# DigitDisplayBoard.net
KiCad netlist of a schematic drawn in EAGLE
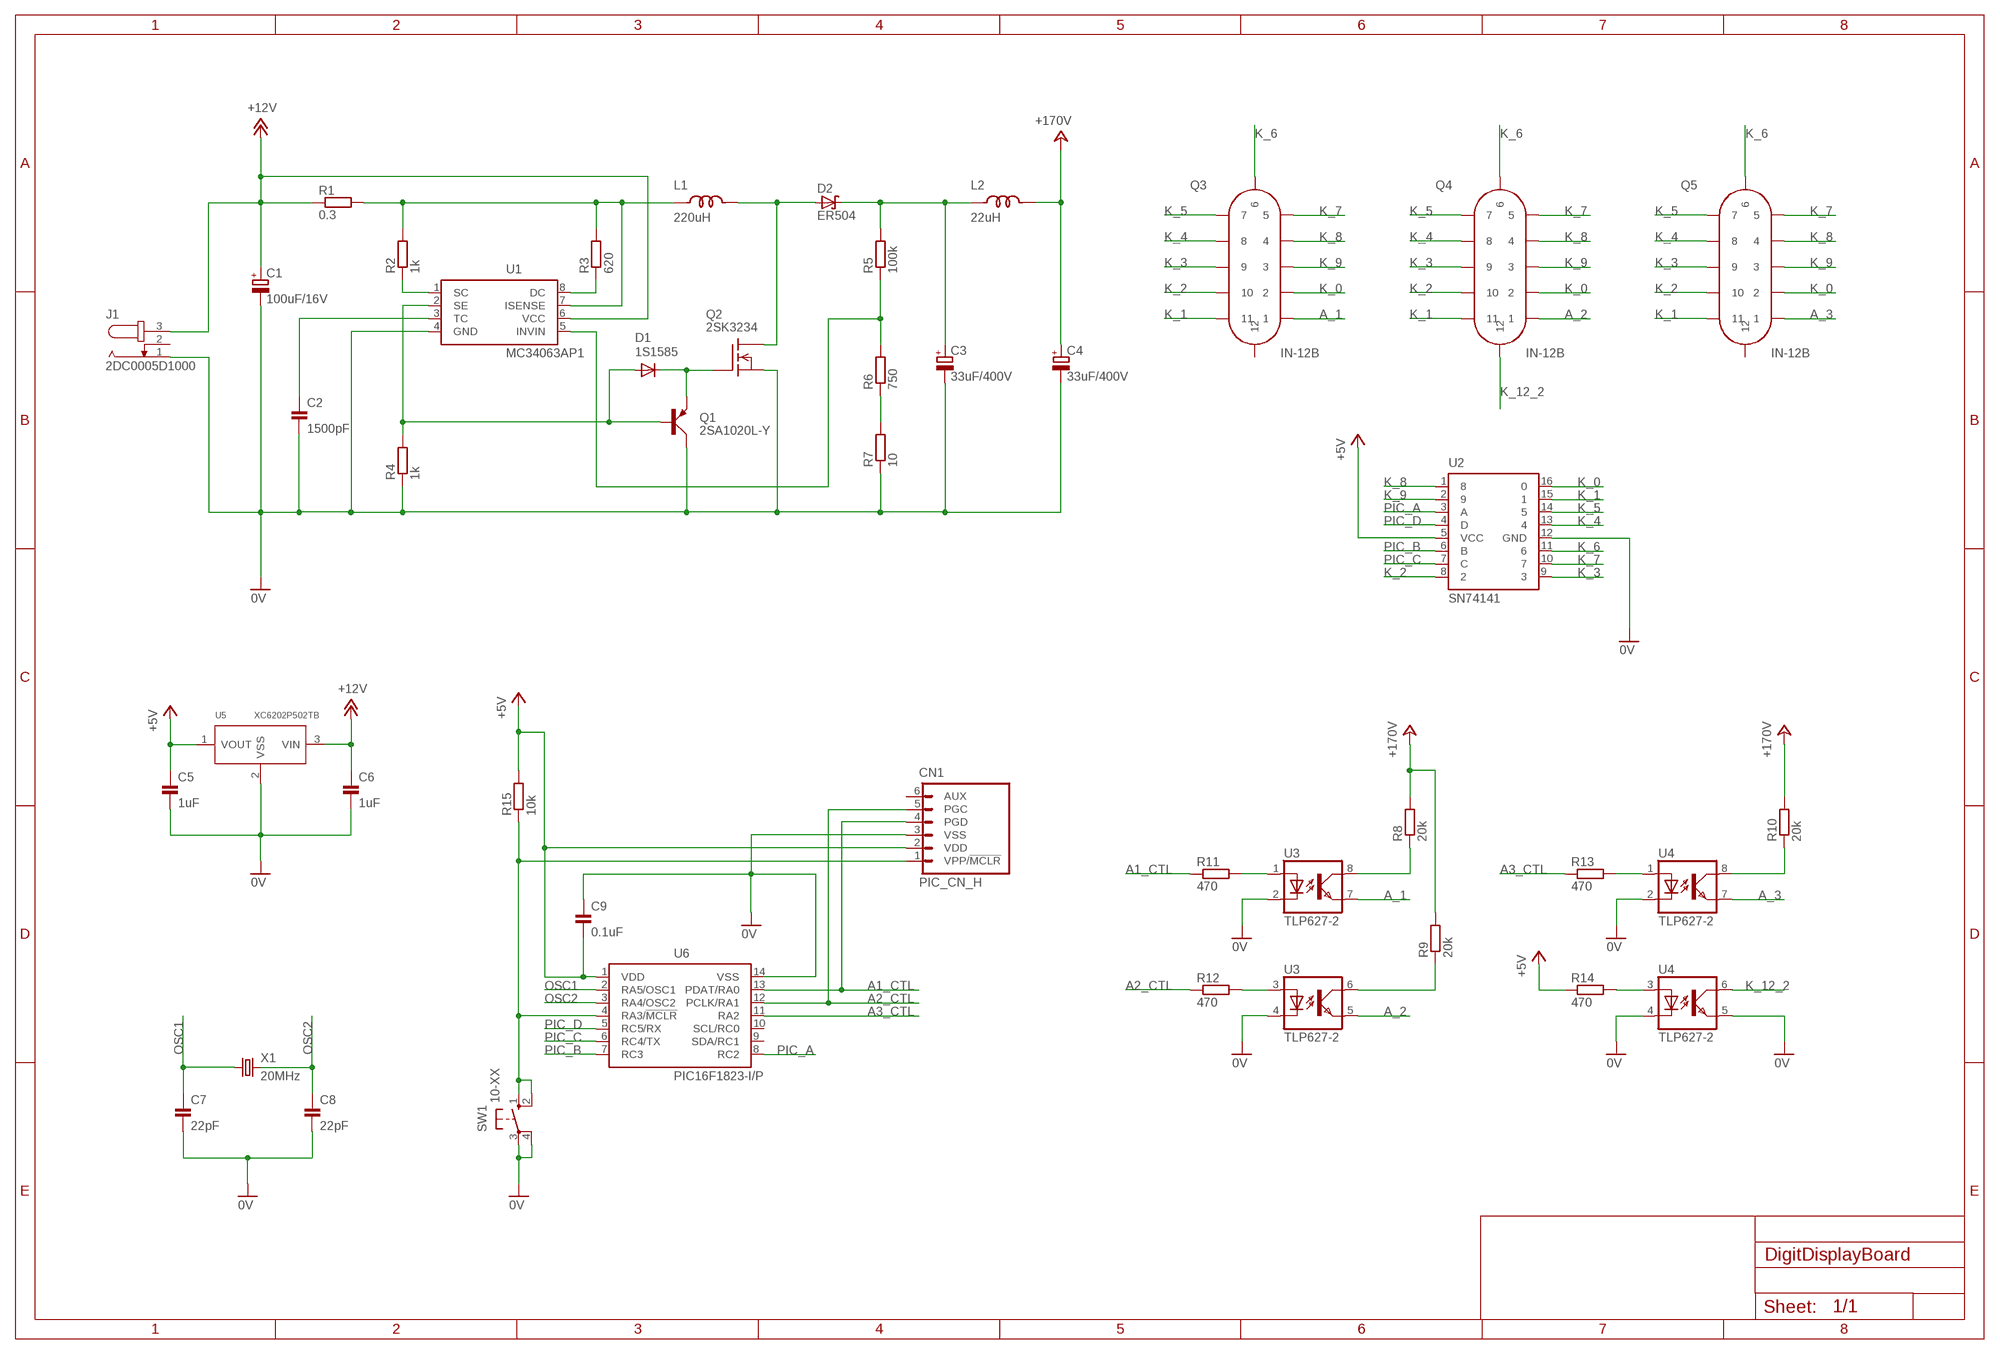
[diagram p0: schematic, sheet 1]

(export (version "E")
  (design (tool "Eeschema 10.0.6"))
  (components
    (comp (ref "C1")
      (value "100uF/16V")
      (footprint "eagle-import:ELECAP_200MIL")
      (libsource (lib "eagle-import") (part "ELECAP_200MIL"))
    )
    (comp (ref "C2")
      (value "1500pF")
      (footprint "eagle-import:CAP_200MIL")
      (libsource (lib "eagle-import") (part "CAP_200MIL"))
    )
    (comp (ref "C3")
      (value "33uF/400V")
      (footprint "eagle-import:ELECAP_300MIL")
      (libsource (lib "eagle-import") (part "ELECAP_300MIL"))
    )
    (comp (ref "C4")
      (value "33uF/400V")
      (footprint "eagle-import:ELECAP_300MIL")
      (libsource (lib "eagle-import") (part "ELECAP_300MIL"))
    )
    (comp (ref "C5")
      (value "1uF")
      (footprint "eagle-import:CAP_200MIL")
      (libsource (lib "eagle-import") (part "CAP_200MIL"))
    )
    (comp (ref "C6")
      (value "1uF")
      (footprint "eagle-import:CAP_200MIL")
      (libsource (lib "eagle-import") (part "CAP_200MIL"))
    )
    (comp (ref "C7")
      (value "22pF")
      (footprint "eagle-import:CAP_200MIL")
      (libsource (lib "eagle-import") (part "CAP_200MIL"))
    )
    (comp (ref "C8")
      (value "22pF")
      (footprint "eagle-import:CAP_200MIL")
      (libsource (lib "eagle-import") (part "CAP_200MIL"))
    )
    (comp (ref "C9")
      (value "0.1uF")
      (footprint "eagle-import:CAP_200MIL")
      (libsource (lib "eagle-import") (part "CAP_200MIL"))
    )
    (comp (ref "CN1")
      (value "PIC_CN_H")
      (footprint "eagle-import:HEADER_6PIN")
      (libsource (lib "eagle-import") (part "PIC_CN_H"))
    )
    (comp (ref "D1")
      (value "1S1585")
      (footprint "eagle-import:DIODE-200MIL")
      (libsource (lib "eagle-import") (part "1S1585"))
    )
    (comp (ref "D2")
      (value "ER504")
      (footprint "eagle-import:DIODE-500MIL")
      (libsource (lib "eagle-import") (part "ER504"))
    )
    (comp (ref "J1")
      (value "2DC0005D1000")
      (footprint "eagle-import:DCJACK_2.1_5.5")
      (libsource (lib "eagle-import") (part "2DC0005D1000"))
    )
    (comp (ref "L1")
      (value "220uH")
      (footprint "eagle-import:TOROID_COIL-300MIL")
      (libsource (lib "eagle-import") (part "TC5026-220UH-050"))
    )
    (comp (ref "L2")
      (value "22uH")
      (footprint "eagle-import:TOROID_COIL-300MIL")
      (libsource (lib "eagle-import") (part "TC5026-22UH-060"))
    )
    (comp (ref "Q1")
      (value "2SA1020L-Y")
      (footprint "eagle-import:TO-92NL")
      (libsource (lib "eagle-import") (part "2SA1020L-Y"))
    )
    (comp (ref "Q2")
      (value "2SK3234")
      (footprint "eagle-import:TO-220")
      (libsource (lib "eagle-import") (part "2SK3234"))
    )
    (comp (ref "Q3")
      (value "IN-12B")
      (footprint "eagle-import:IN-12")
      (libsource (lib "eagle-import") (part "IN-12B"))
    )
    (comp (ref "Q4")
      (value "IN-12B")
      (footprint "eagle-import:IN-12")
      (libsource (lib "eagle-import") (part "IN-12B"))
    )
    (comp (ref "Q5")
      (value "IN-12B")
      (footprint "eagle-import:IN-12")
      (libsource (lib "eagle-import") (part "IN-12B"))
    )
    (comp (ref "R1")
      (value "0.3")
      (footprint "eagle-import:RESISTOR_0411_600MIL")
      (libsource (lib "eagle-import") (part "RESISTOR_600MIL"))
    )
    (comp (ref "R2")
      (value "1k")
      (footprint "eagle-import:RESISTOR_0411_600MIL")
      (libsource (lib "eagle-import") (part "RESISTOR_600MIL"))
    )
    (comp (ref "R3")
      (value "620")
      (footprint "eagle-import:RESISTOR_0411_600MIL")
      (libsource (lib "eagle-import") (part "RESISTOR_600MIL"))
    )
    (comp (ref "R4")
      (value "1k")
      (footprint "eagle-import:RESISTOR_0411_600MIL")
      (libsource (lib "eagle-import") (part "RESISTOR_600MIL"))
    )
    (comp (ref "R5")
      (value "100k")
      (footprint "eagle-import:RESISTOR_0411_600MIL")
      (libsource (lib "eagle-import") (part "RESISTOR_600MIL"))
    )
    (comp (ref "R6")
      (value "750")
      (footprint "eagle-import:RESISTOR_0411_600MIL")
      (libsource (lib "eagle-import") (part "RESISTOR_600MIL"))
    )
    (comp (ref "R7")
      (value "10")
      (footprint "eagle-import:RESISTOR_0411_600MIL")
      (libsource (lib "eagle-import") (part "RESISTOR_600MIL"))
    )
    (comp (ref "R8")
      (value "20k")
      (footprint "eagle-import:RESISTOR_0207_300MIL")
      (libsource (lib "eagle-import") (part "RESISTOR_300MIL"))
    )
    (comp (ref "R9")
      (value "20k")
      (footprint "eagle-import:RESISTOR_0411_600MIL")
      (libsource (lib "eagle-import") (part "RESISTOR_600MIL"))
    )
    (comp (ref "R10")
      (value "20k")
      (footprint "eagle-import:RESISTOR_0207_300MIL")
      (libsource (lib "eagle-import") (part "RESISTOR_300MIL"))
    )
    (comp (ref "R11")
      (value "470")
      (footprint "eagle-import:RESISTOR_0207_300MIL")
      (libsource (lib "eagle-import") (part "RESISTOR_300MIL"))
    )
    (comp (ref "R12")
      (value "470")
      (footprint "eagle-import:RESISTOR_0207_300MIL")
      (libsource (lib "eagle-import") (part "RESISTOR_300MIL"))
    )
    (comp (ref "R13")
      (value "470")
      (footprint "eagle-import:RESISTOR_0207_300MIL")
      (libsource (lib "eagle-import") (part "RESISTOR_300MIL"))
    )
    (comp (ref "R14")
      (value "470")
      (footprint "eagle-import:RESISTOR_0207_300MIL")
      (libsource (lib "eagle-import") (part "RESISTOR_300MIL"))
    )
    (comp (ref "R15")
      (value "10k")
      (footprint "eagle-import:RESISTOR_0207_300MIL")
      (libsource (lib "eagle-import") (part "RESISTOR_300MIL"))
    )
    (comp (ref "SW1")
      (value "10-XX")
      (footprint "eagle-import:B3F-10XX")
      (libsource (lib "eagle-import") (part "10-XX"))
    )
    (comp (ref "U1")
      (value "MC34063AP1")
      (footprint "eagle-import:DIL08")
      (libsource (lib "eagle-import") (part "MC34063AP1"))
    )
    (comp (ref "U2")
      (value "SN74141")
      (footprint "eagle-import:DIL16")
      (libsource (lib "eagle-import") (part "SN74141"))
    )
    (comp (ref "U3")
      (value "TLP627-2")
      (footprint "eagle-import:DIL08")
      (libsource (lib "eagle-import") (part "TLP627-2"))
    )
    (comp (ref "U4")
      (value "TLP627-2")
      (footprint "eagle-import:DIL08")
      (libsource (lib "eagle-import") (part "TLP627-2"))
    )
    (comp (ref "U5")
      (value "XC6202P502TB")
      (footprint "eagle-import:TO92-LINE")
      (libsource (lib "eagle-import") (part "XC6202P502TB"))
    )
    (comp (ref "U6")
      (value "PIC16F1823-I/P")
      (footprint "eagle-import:DIL14")
      (libsource (lib "eagle-import") (part "PIC16F1823-I/P"))
    )
    (comp (ref "X1")
      (value "20MHz")
      (footprint "eagle-import:HC-49_S")
      (libsource (lib "eagle-import") (part "HUSG-20.000-20"))
    )
  )
  (nets
    (net (code "1") (name "+5V") (class "Default")
      (node (ref "C5") (pin "1") (pinfunction "1_1") (pintype "passive"))
      (node (ref "C9") (pin "2") (pinfunction "2_2") (pintype "passive"))
      (node (ref "CN1") (pin "2") (pinfunction "VDD_2") (pintype "passive"))
      (node (ref "R14") (pin "1") (pinfunction "1_1") (pintype "passive"))
      (node (ref "R15") (pin "2") (pinfunction "2_2") (pintype "passive"))
      (node (ref "U2") (pin "5") (pinfunction "VCC_5") (pintype "passive"))
      (node (ref "U5") (pin "1") (pinfunction "VOUT_1") (pintype "passive"))
      (node (ref "U6") (pin "1") (pinfunction "VDD_1") (pintype "passive"))
    )
    (net (code "2") (name "+12V") (class "Default")
      (node (ref "C1") (pin "+") (pinfunction "+_+") (pintype "passive"))
      (node (ref "C6") (pin "1") (pinfunction "1_1") (pintype "passive"))
      (node (ref "J1") (pin "3") (pinfunction "3_3") (pintype "passive"))
      (node (ref "R1") (pin "1") (pinfunction "1_1") (pintype "passive"))
      (node (ref "U1") (pin "6") (pinfunction "VCC_6") (pintype "passive"))
      (node (ref "U5") (pin "3") (pinfunction "VIN_3") (pintype "passive"))
    )
    (net (code "3") (name "+170V") (class "Default")
      (node (ref "C4") (pin "+") (pinfunction "+_+") (pintype "passive"))
      (node (ref "L2") (pin "2") (pinfunction "2_2") (pintype "passive"))
      (node (ref "R10") (pin "2") (pinfunction "2_2") (pintype "passive"))
      (node (ref "R8") (pin "2") (pinfunction "2_2") (pintype "passive"))
      (node (ref "R9") (pin "2") (pinfunction "2_2") (pintype "passive"))
    )
    (net (code "4") (name "/A1_CTL") (class "Default")
      (node (ref "CN1") (pin "4") (pinfunction "PGD_4") (pintype "bidirectional"))
      (node (ref "R11") (pin "1") (pinfunction "1_1") (pintype "passive"))
      (node (ref "U6") (pin "13") (pinfunction "PDAT/RA0_13") (pintype "bidirectional"))
    )
    (net (code "5") (name "/A2_CTL") (class "Default")
      (node (ref "CN1") (pin "5") (pinfunction "PGC_5") (pintype "input"))
      (node (ref "R12") (pin "1") (pinfunction "1_1") (pintype "passive"))
      (node (ref "U6") (pin "12") (pinfunction "PCLK/RA1_12") (pintype "bidirectional"))
    )
    (net (code "6") (name "/A3_CTL") (class "Default")
      (node (ref "R13") (pin "1") (pinfunction "1_1") (pintype "passive"))
      (node (ref "U6") (pin "11") (pinfunction "RA2_11") (pintype "bidirectional"))
    )
    (net (code "7") (name "/A_1") (class "Default")
      (node (ref "Q3") (pin "1") (pinfunction "1_1") (pintype "passive"))
      (node (ref "U3") (pin "7") (pinfunction "EMIT_7") (pintype "passive"))
    )
    (net (code "8") (name "/A_2") (class "Default")
      (node (ref "Q4") (pin "1") (pinfunction "1_1") (pintype "passive"))
      (node (ref "U3") (pin "5") (pinfunction "EMIT_5") (pintype "passive"))
    )
    (net (code "9") (name "/A_3") (class "Default")
      (node (ref "Q5") (pin "1") (pinfunction "1_1") (pintype "passive"))
      (node (ref "U4") (pin "7") (pinfunction "EMIT_7") (pintype "passive"))
    )
    (net (code "10") (name "/K_0") (class "Default")
      (node (ref "Q3") (pin "2") (pinfunction "2_2") (pintype "passive"))
      (node (ref "Q4") (pin "2") (pinfunction "2_2") (pintype "passive"))
      (node (ref "Q5") (pin "2") (pinfunction "2_2") (pintype "passive"))
      (node (ref "U2") (pin "16") (pinfunction "0_16") (pintype "passive"))
    )
    (net (code "11") (name "/K_1") (class "Default")
      (node (ref "Q3") (pin "11") (pinfunction "11_11") (pintype "passive"))
      (node (ref "Q4") (pin "11") (pinfunction "11_11") (pintype "passive"))
      (node (ref "Q5") (pin "11") (pinfunction "11_11") (pintype "passive"))
      (node (ref "U2") (pin "15") (pinfunction "1_15") (pintype "passive"))
    )
    (net (code "12") (name "/K_2") (class "Default")
      (node (ref "Q3") (pin "10") (pinfunction "10_10") (pintype "passive"))
      (node (ref "Q4") (pin "10") (pinfunction "10_10") (pintype "passive"))
      (node (ref "Q5") (pin "10") (pinfunction "10_10") (pintype "passive"))
      (node (ref "U2") (pin "8") (pinfunction "2_8") (pintype "passive"))
    )
    (net (code "13") (name "/K_3") (class "Default")
      (node (ref "Q3") (pin "9") (pinfunction "9_9") (pintype "passive"))
      (node (ref "Q4") (pin "9") (pinfunction "9_9") (pintype "passive"))
      (node (ref "Q5") (pin "9") (pinfunction "9_9") (pintype "passive"))
      (node (ref "U2") (pin "9") (pinfunction "3_9") (pintype "passive"))
    )
    (net (code "14") (name "/K_4") (class "Default")
      (node (ref "Q3") (pin "8") (pinfunction "8_8") (pintype "passive"))
      (node (ref "Q4") (pin "8") (pinfunction "8_8") (pintype "passive"))
      (node (ref "Q5") (pin "8") (pinfunction "8_8") (pintype "passive"))
      (node (ref "U2") (pin "13") (pinfunction "4_13") (pintype "passive"))
    )
    (net (code "15") (name "/K_5") (class "Default")
      (node (ref "Q3") (pin "7") (pinfunction "7_7") (pintype "passive"))
      (node (ref "Q4") (pin "7") (pinfunction "7_7") (pintype "passive"))
      (node (ref "Q5") (pin "7") (pinfunction "7_7") (pintype "passive"))
      (node (ref "U2") (pin "14") (pinfunction "5_14") (pintype "passive"))
    )
    (net (code "16") (name "/K_6") (class "Default")
      (node (ref "Q3") (pin "6") (pinfunction "6_6") (pintype "passive"))
      (node (ref "Q4") (pin "6") (pinfunction "6_6") (pintype "passive"))
      (node (ref "Q5") (pin "6") (pinfunction "6_6") (pintype "passive"))
      (node (ref "U2") (pin "11") (pinfunction "6_11") (pintype "passive"))
    )
    (net (code "17") (name "/K_7") (class "Default")
      (node (ref "Q3") (pin "5") (pinfunction "5_5") (pintype "passive"))
      (node (ref "Q4") (pin "5") (pinfunction "5_5") (pintype "passive"))
      (node (ref "Q5") (pin "5") (pinfunction "5_5") (pintype "passive"))
      (node (ref "U2") (pin "10") (pinfunction "7_10") (pintype "passive"))
    )
    (net (code "18") (name "/K_8") (class "Default")
      (node (ref "Q3") (pin "4") (pinfunction "4_4") (pintype "passive"))
      (node (ref "Q4") (pin "4") (pinfunction "4_4") (pintype "passive"))
      (node (ref "Q5") (pin "4") (pinfunction "4_4") (pintype "passive"))
      (node (ref "U2") (pin "1") (pinfunction "8_1") (pintype "passive"))
    )
    (net (code "19") (name "/K_9") (class "Default")
      (node (ref "Q3") (pin "3") (pinfunction "3_3") (pintype "passive"))
      (node (ref "Q4") (pin "3") (pinfunction "3_3") (pintype "passive"))
      (node (ref "Q5") (pin "3") (pinfunction "3_3") (pintype "passive"))
      (node (ref "U2") (pin "2") (pinfunction "9_2") (pintype "passive"))
    )
    (net (code "20") (name "/K_12_2") (class "Default")
      (node (ref "Q4") (pin "12") (pinfunction "12_12") (pintype "passive"))
      (node (ref "U4") (pin "6") (pinfunction "COL_6") (pintype "passive"))
    )
    (net (code "21") (name "/OSC1") (class "Default")
      (node (ref "C7") (pin "1") (pinfunction "1_1") (pintype "passive"))
      (node (ref "U6") (pin "2") (pinfunction "RA5/OSC1_2") (pintype "bidirectional"))
      (node (ref "X1") (pin "1") (pinfunction "1_1") (pintype "passive"))
    )
    (net (code "22") (name "/OSC2") (class "Default")
      (node (ref "C8") (pin "1") (pinfunction "1_1") (pintype "passive"))
      (node (ref "U6") (pin "3") (pinfunction "RA4/OSC2_3") (pintype "bidirectional"))
      (node (ref "X1") (pin "2") (pinfunction "2_2") (pintype "passive"))
    )
    (net (code "23") (name "/PIC_A") (class "Default")
      (node (ref "U2") (pin "3") (pinfunction "A_3") (pintype "input"))
      (node (ref "U6") (pin "8") (pinfunction "RC2_8") (pintype "bidirectional"))
    )
    (net (code "24") (name "/PIC_B") (class "Default")
      (node (ref "U2") (pin "6") (pinfunction "B_6") (pintype "input"))
      (node (ref "U6") (pin "7") (pinfunction "RC3_7") (pintype "bidirectional"))
    )
    (net (code "25") (name "/PIC_C") (class "Default")
      (node (ref "U2") (pin "7") (pinfunction "C_7") (pintype "input"))
      (node (ref "U6") (pin "6") (pinfunction "RC4/TX_6") (pintype "bidirectional"))
    )
    (net (code "26") (name "/PIC_D") (class "Default")
      (node (ref "U2") (pin "4") (pinfunction "D_4") (pintype "input"))
      (node (ref "U6") (pin "5") (pinfunction "RC5/RX_5") (pintype "bidirectional"))
    )
    (net (code "27") (name "0V") (class "Default")
      (node (ref "C1") (pin "-") (pinfunction "-_-") (pintype "passive"))
      (node (ref "C2") (pin "2") (pinfunction "2_2") (pintype "passive"))
      (node (ref "C3") (pin "-") (pinfunction "-_-") (pintype "passive"))
      (node (ref "C4") (pin "-") (pinfunction "-_-") (pintype "passive"))
      (node (ref "C5") (pin "2") (pinfunction "2_2") (pintype "passive"))
      (node (ref "C6") (pin "2") (pinfunction "2_2") (pintype "passive"))
      (node (ref "C7") (pin "2") (pinfunction "2_2") (pintype "passive"))
      (node (ref "C8") (pin "2") (pinfunction "2_2") (pintype "passive"))
      (node (ref "C9") (pin "1") (pinfunction "1_1") (pintype "passive"))
      (node (ref "CN1") (pin "3") (pinfunction "VSS_3") (pintype "passive"))
      (node (ref "J1") (pin "1") (pinfunction "1_1") (pintype "passive"))
      (node (ref "Q1") (pin "2") (pinfunction "C_2") (pintype "passive"))
      (node (ref "Q2") (pin "3") (pinfunction "S_3") (pintype "passive"))
      (node (ref "R4") (pin "1") (pinfunction "1_1") (pintype "passive"))
      (node (ref "R7") (pin "1") (pinfunction "1_1") (pintype "passive"))
      (node (ref "SW1") (pin "3") (pinfunction "P_3") (pintype "passive"))
      (node (ref "SW1") (pin "4") (pinfunction "P1_4") (pintype "passive"))
      (node (ref "U1") (pin "4") (pinfunction "GND_4") (pintype "passive"))
      (node (ref "U2") (pin "12") (pinfunction "GND_12") (pintype "passive"))
      (node (ref "U3") (pin "2") (pinfunction "C_2") (pintype "passive"))
      (node (ref "U3") (pin "4") (pinfunction "C_4") (pintype "passive"))
      (node (ref "U4") (pin "2") (pinfunction "C_2") (pintype "passive"))
      (node (ref "U4") (pin "4") (pinfunction "C_4") (pintype "passive"))
      (node (ref "U4") (pin "5") (pinfunction "EMIT_5") (pintype "passive"))
      (node (ref "U5") (pin "2") (pinfunction "VSS_2") (pintype "passive"))
      (node (ref "U6") (pin "14") (pinfunction "VSS_14") (pintype "passive"))
    )
    (net (code "28") (name "Net-(C3-Pad+)") (class "Default")
      (node (ref "C3") (pin "+") (pinfunction "+_+") (pintype "passive"))
      (node (ref "D2") (pin "C") (pinfunction "C_C") (pintype "passive"))
      (node (ref "L2") (pin "1") (pinfunction "1_1") (pintype "passive"))
      (node (ref "R5") (pin "2") (pinfunction "2_2") (pintype "passive"))
    )
    (net (code "29") (name "Net-(CN1-VPP{slash}~{MCLR})") (class "Default")
      (node (ref "CN1") (pin "1") (pinfunction "VPP/~{MCLR}_1") (pintype "input"))
      (node (ref "R15") (pin "1") (pinfunction "1_1") (pintype "passive"))
      (node (ref "SW1") (pin "1") (pinfunction "S_1") (pintype "passive"))
      (node (ref "SW1") (pin "2") (pinfunction "S1_2") (pintype "passive"))
      (node (ref "U6") (pin "4") (pinfunction "RA3/~{MCLR}_4") (pintype "bidirectional"))
    )
    (net (code "30") (name "Net-(Q1-B)") (class "Default")
      (node (ref "D1") (pin "A") (pinfunction "A_A") (pintype "passive"))
      (node (ref "Q1") (pin "3") (pinfunction "B_3") (pintype "passive"))
      (node (ref "R4") (pin "2") (pinfunction "2_2") (pintype "passive"))
      (node (ref "U1") (pin "2") (pinfunction "SE_2") (pintype "passive"))
    )
    (net (code "31") (name "Net-(Q1-E)") (class "Default")
      (node (ref "D1") (pin "C") (pinfunction "C_C") (pintype "passive"))
      (node (ref "Q1") (pin "1") (pinfunction "E_1") (pintype "passive"))
      (node (ref "Q2") (pin "1") (pinfunction "G_1") (pintype "passive"))
    )
    (net (code "32") (name "Net-(Q2-D)") (class "Default")
      (node (ref "D2") (pin "A") (pinfunction "A_A") (pintype "passive"))
      (node (ref "L1") (pin "2") (pinfunction "2_2") (pintype "passive"))
      (node (ref "Q2") (pin "2") (pinfunction "D_2") (pintype "passive"))
    )
    (net (code "33") (name "Net-(R6-Pad1)") (class "Default")
      (node (ref "R6") (pin "1") (pinfunction "1_1") (pintype "passive"))
      (node (ref "R7") (pin "2") (pinfunction "2_2") (pintype "passive"))
    )
    (net (code "34") (name "Net-(U1-DC)") (class "Default")
      (node (ref "R3") (pin "1") (pinfunction "1_1") (pintype "passive"))
      (node (ref "U1") (pin "8") (pinfunction "DC_8") (pintype "passive"))
    )
    (net (code "35") (name "Net-(U1-INVIN)") (class "Default")
      (node (ref "R5") (pin "1") (pinfunction "1_1") (pintype "passive"))
      (node (ref "R6") (pin "2") (pinfunction "2_2") (pintype "passive"))
      (node (ref "U1") (pin "5") (pinfunction "INVIN_5") (pintype "passive"))
    )
    (net (code "36") (name "Net-(U1-ISENSE)") (class "Default")
      (node (ref "L1") (pin "1") (pinfunction "1_1") (pintype "passive"))
      (node (ref "R1") (pin "2") (pinfunction "2_2") (pintype "passive"))
      (node (ref "R2") (pin "2") (pinfunction "2_2") (pintype "passive"))
      (node (ref "R3") (pin "2") (pinfunction "2_2") (pintype "passive"))
      (node (ref "U1") (pin "7") (pinfunction "ISENSE_7") (pintype "passive"))
    )
    (net (code "37") (name "Net-(U1-SC)") (class "Default")
      (node (ref "R2") (pin "1") (pinfunction "1_1") (pintype "passive"))
      (node (ref "U1") (pin "1") (pinfunction "SC_1") (pintype "passive"))
    )
    (net (code "38") (name "Net-(U1-TC)") (class "Default")
      (node (ref "C2") (pin "1") (pinfunction "1_1") (pintype "passive"))
      (node (ref "U1") (pin "3") (pinfunction "TC_3") (pintype "passive"))
    )
    (net (code "39") (name "Net-(U3A-A)") (class "Default")
      (node (ref "R11") (pin "2") (pinfunction "2_2") (pintype "passive"))
      (node (ref "U3") (pin "1") (pinfunction "A_1") (pintype "passive"))
    )
    (net (code "40") (name "Net-(U3A-COL)") (class "Default")
      (node (ref "R8") (pin "1") (pinfunction "1_1") (pintype "passive"))
      (node (ref "U3") (pin "8") (pinfunction "COL_8") (pintype "passive"))
    )
    (net (code "41") (name "Net-(U3B-A)") (class "Default")
      (node (ref "R12") (pin "2") (pinfunction "2_2") (pintype "passive"))
      (node (ref "U3") (pin "3") (pinfunction "A_3") (pintype "passive"))
    )
    (net (code "42") (name "Net-(U3B-COL)") (class "Default")
      (node (ref "R9") (pin "1") (pinfunction "1_1") (pintype "passive"))
      (node (ref "U3") (pin "6") (pinfunction "COL_6") (pintype "passive"))
    )
    (net (code "43") (name "Net-(U4A-A)") (class "Default")
      (node (ref "R13") (pin "2") (pinfunction "2_2") (pintype "passive"))
      (node (ref "U4") (pin "1") (pinfunction "A_1") (pintype "passive"))
    )
    (net (code "44") (name "Net-(U4A-COL)") (class "Default")
      (node (ref "R10") (pin "1") (pinfunction "1_1") (pintype "passive"))
      (node (ref "U4") (pin "8") (pinfunction "COL_8") (pintype "passive"))
    )
    (net (code "45") (name "Net-(U4B-A)") (class "Default")
      (node (ref "R14") (pin "2") (pinfunction "2_2") (pintype "passive"))
      (node (ref "U4") (pin "3") (pinfunction "A_3") (pintype "passive"))
    )
    (net (code "46") (name "unconnected-(CN1-AUX-Pad6)") (class "Default")
      (node (ref "CN1") (pin "6") (pinfunction "AUX_6") (pintype "bidirectional"))
    )
    (net (code "47") (name "unconnected-(J1-Pad2)") (class "Default")
      (node (ref "J1") (pin "2") (pinfunction "2_2") (pintype "passive"))
    )
    (net (code "48") (name "unconnected-(Q3-Pad12)") (class "Default")
      (node (ref "Q3") (pin "12") (pinfunction "12_12") (pintype "passive"))
    )
    (net (code "49") (name "unconnected-(Q5-Pad12)") (class "Default")
      (node (ref "Q5") (pin "12") (pinfunction "12_12") (pintype "passive"))
    )
    (net (code "50") (name "unconnected-(U6-SCL{slash}RC0-Pad10)") (class "Default")
      (node (ref "U6") (pin "10") (pinfunction "SCL/RC0_10") (pintype "bidirectional"))
    )
    (net (code "51") (name "unconnected-(U6-SDA{slash}RC1-Pad9)") (class "Default")
      (node (ref "U6") (pin "9") (pinfunction "SDA/RC1_9") (pintype "bidirectional"))
    )
  )
)
